# battleship.net
KiCad netlist of a schematic drawn in EAGLE
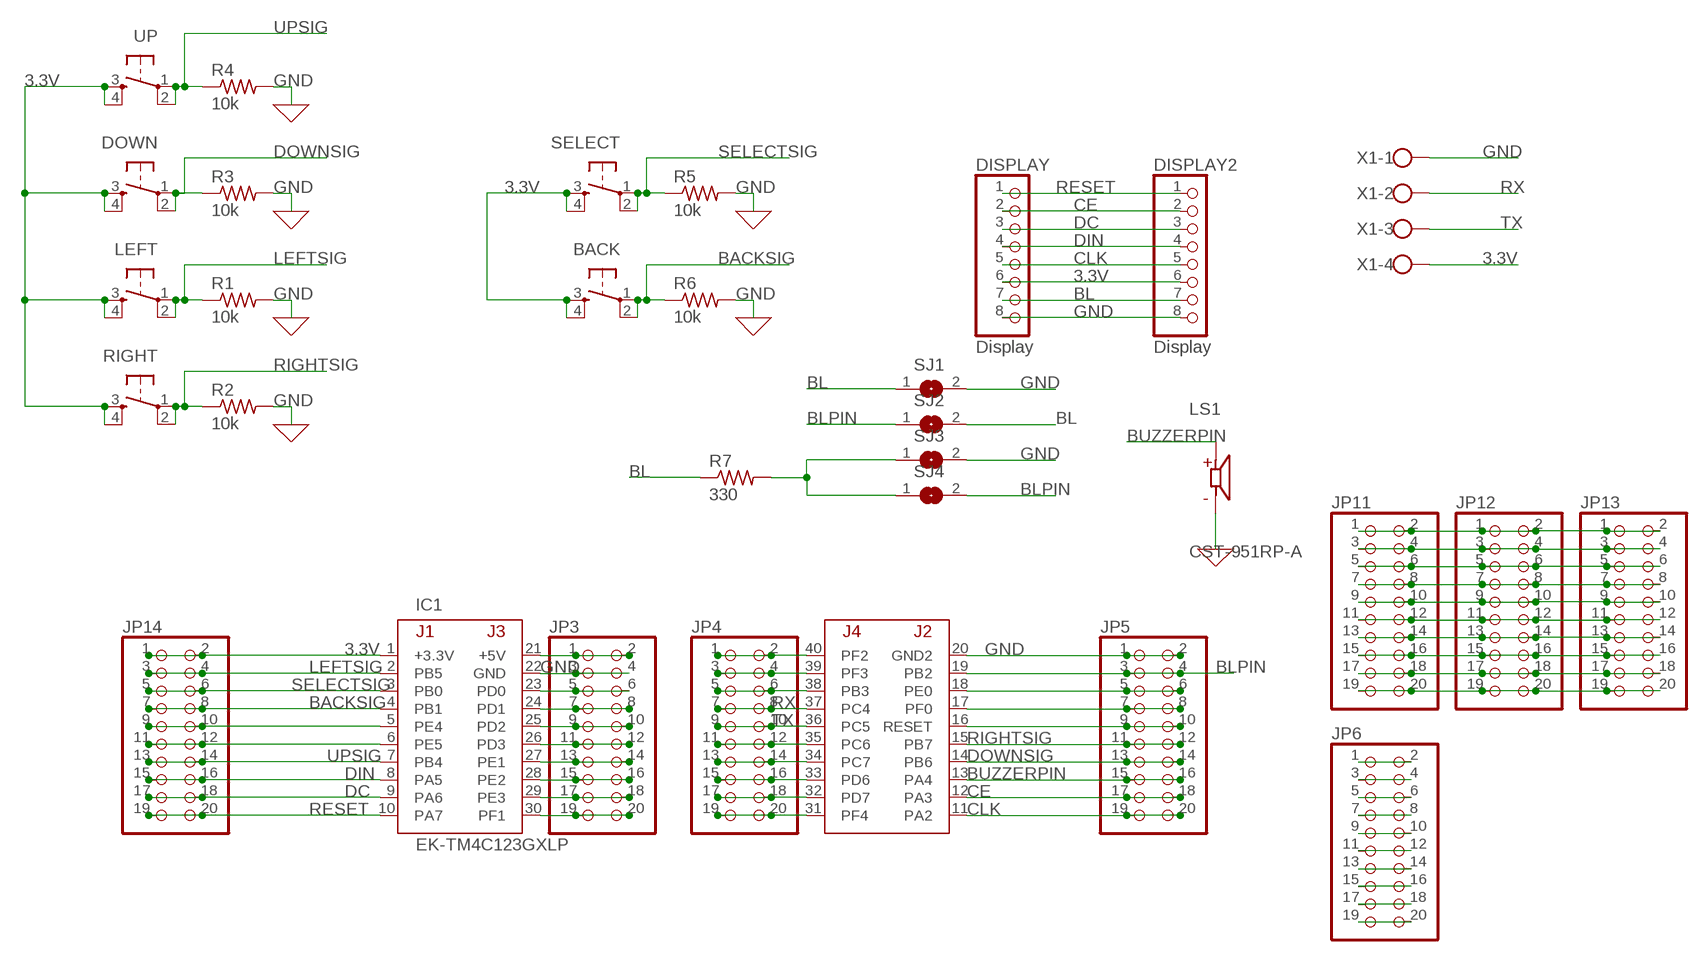
[diagram p0: schematic, sheet 1]

(export (version "E")
  (design (tool "Eeschema 10.0.6"))
  (components
    (comp (ref "BACK")
      (value "TAC_SWITCHPTH")
      (footprint "eagle-import:TACTILE-PTH")
      (libsource (lib "eagle-import") (part "TAC_SWITCHPTH"))
    )
    (comp (ref "DISPLAY")
      (value "Display")
      (footprint "eagle-import:1X08")
      (libsource (lib "eagle-import") (part "PINHD-1X8"))
    )
    (comp (ref "DISPLAY2")
      (value "Display")
      (footprint "eagle-import:1X08")
      (libsource (lib "eagle-import") (part "PINHD-1X8"))
    )
    (comp (ref "DOWN")
      (value "TAC_SWITCHPTH")
      (footprint "eagle-import:TACTILE-PTH")
      (libsource (lib "eagle-import") (part "TAC_SWITCHPTH"))
    )
    (comp (ref "IC1")
      (value "EK-TM4C123GXLP")
      (footprint "eagle-import:TM4C123LAUNCHPAD")
      (libsource (lib "eagle-import") (part "EK-TM4C123GXLP"))
    )
    (comp (ref "JP3")
      (value "PINHD-2X10")
      (footprint "eagle-import:2X10")
      (libsource (lib "eagle-import") (part "PINHD-2X10"))
    )
    (comp (ref "JP4")
      (value "PINHD-2X10")
      (footprint "eagle-import:2X10")
      (libsource (lib "eagle-import") (part "PINHD-2X10"))
    )
    (comp (ref "JP5")
      (value "PINHD-2X10")
      (footprint "eagle-import:2X10")
      (libsource (lib "eagle-import") (part "PINHD-2X10"))
    )
    (comp (ref "JP6")
      (value "PINHD-2X10")
      (footprint "eagle-import:2X10")
      (libsource (lib "eagle-import") (part "PINHD-2X10"))
    )
    (comp (ref "JP11")
      (value "PINHD-2X10")
      (footprint "eagle-import:2X10")
      (libsource (lib "eagle-import") (part "PINHD-2X10"))
    )
    (comp (ref "JP12")
      (value "PINHD-2X10")
      (footprint "eagle-import:2X10")
      (libsource (lib "eagle-import") (part "PINHD-2X10"))
    )
    (comp (ref "JP13")
      (value "PINHD-2X10")
      (footprint "eagle-import:2X10")
      (libsource (lib "eagle-import") (part "PINHD-2X10"))
    )
    (comp (ref "JP14")
      (value "PINHD-2X10")
      (footprint "eagle-import:2X10")
      (libsource (lib "eagle-import") (part "PINHD-2X10"))
    )
    (comp (ref "LEFT")
      (value "TAC_SWITCHPTH")
      (footprint "eagle-import:TACTILE-PTH")
      (libsource (lib "eagle-import") (part "TAC_SWITCHPTH"))
    )
    (comp (ref "LS1")
      (value "CST-951RP-A")
      (footprint "eagle-import:CUI_CST-951RP-A")
      (fields (field (name "MF") "CUI Inc."))
      (libsource (lib "eagle-import") (part "CST-951RP-A"))
    )
    (comp (ref "R1")
      (value "10k")
      (footprint "eagle-import:0207_10")
      (libsource (lib "eagle-import") (part "R-US_0207/10"))
    )
    (comp (ref "R2")
      (value "10k")
      (footprint "eagle-import:0207_10")
      (libsource (lib "eagle-import") (part "R-US_0207/10"))
    )
    (comp (ref "R3")
      (value "10k")
      (footprint "eagle-import:0207_10")
      (libsource (lib "eagle-import") (part "R-US_0207/10"))
    )
    (comp (ref "R4")
      (value "10k")
      (footprint "eagle-import:0207_10")
      (libsource (lib "eagle-import") (part "R-US_0207/10"))
    )
    (comp (ref "R5")
      (value "10k")
      (footprint "eagle-import:0207_10")
      (libsource (lib "eagle-import") (part "R-US_0207/10"))
    )
    (comp (ref "R6")
      (value "10k")
      (footprint "eagle-import:0207_10")
      (libsource (lib "eagle-import") (part "R-US_0207/10"))
    )
    (comp (ref "R7")
      (value "330")
      (footprint "eagle-import:0207_10")
      (libsource (lib "eagle-import") (part "R-US_0207/10"))
    )
    (comp (ref "RIGHT")
      (value "TAC_SWITCHPTH")
      (footprint "eagle-import:TACTILE-PTH")
      (libsource (lib "eagle-import") (part "TAC_SWITCHPTH"))
    )
    (comp (ref "SELECT")
      (value "TAC_SWITCHPTH")
      (footprint "eagle-import:TACTILE-PTH")
      (libsource (lib "eagle-import") (part "TAC_SWITCHPTH"))
    )
    (comp (ref "SJ1") (value "SJ") (footprint "eagle-import:SJ") (libsource (lib "eagle-import") (part "SJ")))
    (comp (ref "SJ2") (value "SJ") (footprint "eagle-import:SJ") (libsource (lib "eagle-import") (part "SJ")))
    (comp (ref "SJ3") (value "SJ") (footprint "eagle-import:SJ") (libsource (lib "eagle-import") (part "SJ")))
    (comp (ref "SJ4") (value "SJ") (footprint "eagle-import:SJ") (libsource (lib "eagle-import") (part "SJ")))
    (comp (ref "UP")
      (value "TAC_SWITCHPTH")
      (footprint "eagle-import:TACTILE-PTH")
      (libsource (lib "eagle-import") (part "TAC_SWITCHPTH"))
    )
    (comp (ref "X1")
      (value "W237-4")
      (footprint "eagle-import:W237-4")
      (libsource (lib "eagle-import") (part "W237-4"))
    )
  )
  (nets
    (net (code "1") (name "/3.3V") (class "Default")
      (node (ref "BACK") (pin "3") (pinfunction "3_3") (pintype "passive"))
      (node (ref "BACK") (pin "4") (pinfunction "4_4") (pintype "passive"))
      (node (ref "DISPLAY") (pin "6") (pinfunction "6_6") (pintype "passive"))
      (node (ref "DISPLAY2") (pin "6") (pinfunction "6_6") (pintype "passive"))
      (node (ref "DOWN") (pin "3") (pinfunction "3_3") (pintype "passive"))
      (node (ref "DOWN") (pin "4") (pinfunction "4_4") (pintype "passive"))
      (node (ref "IC1") (pin "1") (pinfunction "+3.3V_1") (pintype "power_in"))
      (node (ref "JP14") (pin "1") (pinfunction "1_1") (pintype "passive"))
      (node (ref "JP14") (pin "2") (pinfunction "2_2") (pintype "passive"))
      (node (ref "LEFT") (pin "3") (pinfunction "3_3") (pintype "passive"))
      (node (ref "LEFT") (pin "4") (pinfunction "4_4") (pintype "passive"))
      (node (ref "RIGHT") (pin "3") (pinfunction "3_3") (pintype "passive"))
      (node (ref "RIGHT") (pin "4") (pinfunction "4_4") (pintype "passive"))
      (node (ref "SELECT") (pin "3") (pinfunction "3_3") (pintype "passive"))
      (node (ref "SELECT") (pin "4") (pinfunction "4_4") (pintype "passive"))
      (node (ref "UP") (pin "3") (pinfunction "3_3") (pintype "passive"))
      (node (ref "UP") (pin "4") (pinfunction "4_4") (pintype "passive"))
      (node (ref "X1") (pin "4") (pinfunction "KL_4") (pintype "passive"))
    )
    (net (code "2") (name "/BACKSIG") (class "Default")
      (node (ref "BACK") (pin "1") (pinfunction "1_1") (pintype "passive"))
      (node (ref "BACK") (pin "2") (pinfunction "2_2") (pintype "passive"))
      (node (ref "IC1") (pin "4") (pinfunction "PB1_4") (pintype "bidirectional"))
      (node (ref "JP14") (pin "7") (pinfunction "7_7") (pintype "passive"))
      (node (ref "JP14") (pin "8") (pinfunction "8_8") (pintype "passive"))
      (node (ref "R6") (pin "1") (pinfunction "1_1") (pintype "passive"))
    )
    (net (code "3") (name "/BL") (class "Default")
      (node (ref "DISPLAY") (pin "7") (pinfunction "7_7") (pintype "passive"))
      (node (ref "DISPLAY2") (pin "7") (pinfunction "7_7") (pintype "passive"))
      (node (ref "R7") (pin "1") (pinfunction "1_1") (pintype "passive"))
      (node (ref "SJ1") (pin "1") (pinfunction "1_1") (pintype "passive"))
      (node (ref "SJ2") (pin "2") (pinfunction "2_2") (pintype "passive"))
    )
    (net (code "4") (name "/BLPIN") (class "Default")
      (node (ref "IC1") (pin "19") (pinfunction "PB2_19") (pintype "bidirectional"))
      (node (ref "JP5") (pin "3") (pinfunction "3_3") (pintype "passive"))
      (node (ref "JP5") (pin "4") (pinfunction "4_4") (pintype "passive"))
      (node (ref "SJ2") (pin "1") (pinfunction "1_1") (pintype "passive"))
      (node (ref "SJ4") (pin "2") (pinfunction "2_2") (pintype "passive"))
    )
    (net (code "5") (name "/BUZZERPIN") (class "Default")
      (node (ref "IC1") (pin "13") (pinfunction "PA4_13") (pintype "bidirectional"))
      (node (ref "JP5") (pin "15") (pinfunction "15_15") (pintype "passive"))
      (node (ref "JP5") (pin "16") (pinfunction "16_16") (pintype "passive"))
      (node (ref "LS1") (pin "P") (pinfunction "P_P") (pintype "passive"))
    )
    (net (code "6") (name "/CE") (class "Default")
      (node (ref "DISPLAY") (pin "2") (pinfunction "2_2") (pintype "passive"))
      (node (ref "DISPLAY2") (pin "2") (pinfunction "2_2") (pintype "passive"))
      (node (ref "IC1") (pin "12") (pinfunction "PA3_12") (pintype "bidirectional"))
      (node (ref "JP5") (pin "17") (pinfunction "17_17") (pintype "passive"))
      (node (ref "JP5") (pin "18") (pinfunction "18_18") (pintype "passive"))
    )
    (net (code "7") (name "/CLK") (class "Default")
      (node (ref "DISPLAY") (pin "5") (pinfunction "5_5") (pintype "passive"))
      (node (ref "DISPLAY2") (pin "5") (pinfunction "5_5") (pintype "passive"))
      (node (ref "IC1") (pin "11") (pinfunction "PA2_11") (pintype "bidirectional"))
      (node (ref "JP5") (pin "19") (pinfunction "19_19") (pintype "passive"))
      (node (ref "JP5") (pin "20") (pinfunction "20_20") (pintype "passive"))
    )
    (net (code "8") (name "/DC") (class "Default")
      (node (ref "DISPLAY") (pin "3") (pinfunction "3_3") (pintype "passive"))
      (node (ref "DISPLAY2") (pin "3") (pinfunction "3_3") (pintype "passive"))
      (node (ref "IC1") (pin "9") (pinfunction "PA6_9") (pintype "bidirectional"))
      (node (ref "JP14") (pin "17") (pinfunction "17_17") (pintype "passive"))
      (node (ref "JP14") (pin "18") (pinfunction "18_18") (pintype "passive"))
    )
    (net (code "9") (name "/DIN") (class "Default")
      (node (ref "DISPLAY") (pin "4") (pinfunction "4_4") (pintype "passive"))
      (node (ref "DISPLAY2") (pin "4") (pinfunction "4_4") (pintype "passive"))
      (node (ref "IC1") (pin "8") (pinfunction "PA5_8") (pintype "bidirectional"))
      (node (ref "JP14") (pin "15") (pinfunction "15_15") (pintype "passive"))
      (node (ref "JP14") (pin "16") (pinfunction "16_16") (pintype "passive"))
    )
    (net (code "10") (name "/DOWNSIG") (class "Default")
      (node (ref "DOWN") (pin "1") (pinfunction "1_1") (pintype "passive"))
      (node (ref "DOWN") (pin "2") (pinfunction "2_2") (pintype "passive"))
      (node (ref "IC1") (pin "14") (pinfunction "PB6_14") (pintype "bidirectional"))
      (node (ref "JP5") (pin "13") (pinfunction "13_13") (pintype "passive"))
      (node (ref "JP5") (pin "14") (pinfunction "14_14") (pintype "passive"))
      (node (ref "R3") (pin "1") (pinfunction "1_1") (pintype "passive"))
    )
    (net (code "11") (name "/LEFTSIG") (class "Default")
      (node (ref "IC1") (pin "2") (pinfunction "PB5_2") (pintype "bidirectional"))
      (node (ref "JP14") (pin "3") (pinfunction "3_3") (pintype "passive"))
      (node (ref "JP14") (pin "4") (pinfunction "4_4") (pintype "passive"))
      (node (ref "LEFT") (pin "1") (pinfunction "1_1") (pintype "passive"))
      (node (ref "LEFT") (pin "2") (pinfunction "2_2") (pintype "passive"))
      (node (ref "R1") (pin "1") (pinfunction "1_1") (pintype "passive"))
    )
    (net (code "12") (name "/RESET") (class "Default")
      (node (ref "DISPLAY") (pin "1") (pinfunction "1_1") (pintype "passive"))
      (node (ref "DISPLAY2") (pin "1") (pinfunction "1_1") (pintype "passive"))
      (node (ref "IC1") (pin "10") (pinfunction "PA7_10") (pintype "bidirectional"))
      (node (ref "JP14") (pin "19") (pinfunction "19_19") (pintype "passive"))
      (node (ref "JP14") (pin "20") (pinfunction "20_20") (pintype "passive"))
    )
    (net (code "13") (name "/RIGHTSIG") (class "Default")
      (node (ref "IC1") (pin "15") (pinfunction "PB7_15") (pintype "bidirectional"))
      (node (ref "JP5") (pin "11") (pinfunction "11_11") (pintype "passive"))
      (node (ref "JP5") (pin "12") (pinfunction "12_12") (pintype "passive"))
      (node (ref "R2") (pin "1") (pinfunction "1_1") (pintype "passive"))
      (node (ref "RIGHT") (pin "1") (pinfunction "1_1") (pintype "passive"))
      (node (ref "RIGHT") (pin "2") (pinfunction "2_2") (pintype "passive"))
    )
    (net (code "14") (name "/RX") (class "Default")
      (node (ref "IC1") (pin "37") (pinfunction "PC4_37") (pintype "bidirectional"))
      (node (ref "JP4") (pin "7") (pinfunction "7_7") (pintype "passive"))
      (node (ref "JP4") (pin "8") (pinfunction "8_8") (pintype "passive"))
      (node (ref "X1") (pin "2") (pinfunction "KL_2") (pintype "passive"))
    )
    (net (code "15") (name "/SELECTSIG") (class "Default")
      (node (ref "IC1") (pin "3") (pinfunction "PB0_3") (pintype "bidirectional"))
      (node (ref "JP14") (pin "5") (pinfunction "5_5") (pintype "passive"))
      (node (ref "JP14") (pin "6") (pinfunction "6_6") (pintype "passive"))
      (node (ref "R5") (pin "1") (pinfunction "1_1") (pintype "passive"))
      (node (ref "SELECT") (pin "1") (pinfunction "1_1") (pintype "passive"))
      (node (ref "SELECT") (pin "2") (pinfunction "2_2") (pintype "passive"))
    )
    (net (code "16") (name "/TX") (class "Default")
      (node (ref "IC1") (pin "36") (pinfunction "PC5_36") (pintype "bidirectional"))
      (node (ref "JP4") (pin "10") (pinfunction "10_10") (pintype "passive"))
      (node (ref "JP4") (pin "9") (pinfunction "9_9") (pintype "passive"))
      (node (ref "X1") (pin "3") (pinfunction "KL_3") (pintype "passive"))
    )
    (net (code "17") (name "/UPSIG") (class "Default")
      (node (ref "IC1") (pin "7") (pinfunction "PB4_7") (pintype "bidirectional"))
      (node (ref "JP14") (pin "13") (pinfunction "13_13") (pintype "passive"))
      (node (ref "JP14") (pin "14") (pinfunction "14_14") (pintype "passive"))
      (node (ref "R4") (pin "1") (pinfunction "1_1") (pintype "passive"))
      (node (ref "UP") (pin "1") (pinfunction "1_1") (pintype "passive"))
      (node (ref "UP") (pin "2") (pinfunction "2_2") (pintype "passive"))
    )
    (net (code "18") (name "GND") (class "Default")
      (node (ref "DISPLAY") (pin "8") (pinfunction "8_8") (pintype "passive"))
      (node (ref "DISPLAY2") (pin "8") (pinfunction "8_8") (pintype "passive"))
      (node (ref "IC1") (pin "20") (pinfunction "GND2_20") (pintype "power_in"))
      (node (ref "IC1") (pin "22") (pinfunction "GND_22") (pintype "power_in"))
      (node (ref "JP3") (pin "3") (pinfunction "3_3") (pintype "passive"))
      (node (ref "JP3") (pin "4") (pinfunction "4_4") (pintype "passive"))
      (node (ref "JP5") (pin "1") (pinfunction "1_1") (pintype "passive"))
      (node (ref "JP5") (pin "2") (pinfunction "2_2") (pintype "passive"))
      (node (ref "LS1") (pin "M") (pinfunction "M_M") (pintype "passive"))
      (node (ref "R1") (pin "2") (pinfunction "2_2") (pintype "passive"))
      (node (ref "R2") (pin "2") (pinfunction "2_2") (pintype "passive"))
      (node (ref "R3") (pin "2") (pinfunction "2_2") (pintype "passive"))
      (node (ref "R4") (pin "2") (pinfunction "2_2") (pintype "passive"))
      (node (ref "R5") (pin "2") (pinfunction "2_2") (pintype "passive"))
      (node (ref "R6") (pin "2") (pinfunction "2_2") (pintype "passive"))
      (node (ref "SJ1") (pin "2") (pinfunction "2_2") (pintype "passive"))
      (node (ref "SJ3") (pin "2") (pinfunction "2_2") (pintype "passive"))
      (node (ref "X1") (pin "1") (pinfunction "KL_1") (pintype "passive"))
    )
    (net (code "19") (name "Net-(IC1-+5V)") (class "Default")
      (node (ref "IC1") (pin "21") (pinfunction "+5V_21") (pintype "power_in"))
      (node (ref "JP3") (pin "1") (pinfunction "1_1") (pintype "passive"))
      (node (ref "JP3") (pin "2") (pinfunction "2_2") (pintype "passive"))
    )
    (net (code "20") (name "Net-(IC1-PB3)") (class "Default")
      (node (ref "IC1") (pin "38") (pinfunction "PB3_38") (pintype "bidirectional"))
      (node (ref "JP4") (pin "5") (pinfunction "5_5") (pintype "passive"))
      (node (ref "JP4") (pin "6") (pinfunction "6_6") (pintype "passive"))
    )
    (net (code "21") (name "Net-(IC1-PC6)") (class "Default")
      (node (ref "IC1") (pin "35") (pinfunction "PC6_35") (pintype "bidirectional"))
      (node (ref "JP4") (pin "11") (pinfunction "11_11") (pintype "passive"))
      (node (ref "JP4") (pin "12") (pinfunction "12_12") (pintype "passive"))
    )
    (net (code "22") (name "Net-(IC1-PC7)") (class "Default")
      (node (ref "IC1") (pin "34") (pinfunction "PC7_34") (pintype "bidirectional"))
      (node (ref "JP4") (pin "13") (pinfunction "13_13") (pintype "passive"))
      (node (ref "JP4") (pin "14") (pinfunction "14_14") (pintype "passive"))
    )
    (net (code "23") (name "Net-(IC1-PD0)") (class "Default")
      (node (ref "IC1") (pin "23") (pinfunction "PD0_23") (pintype "bidirectional"))
      (node (ref "JP3") (pin "5") (pinfunction "5_5") (pintype "passive"))
      (node (ref "JP3") (pin "6") (pinfunction "6_6") (pintype "passive"))
    )
    (net (code "24") (name "Net-(IC1-PD1)") (class "Default")
      (node (ref "IC1") (pin "24") (pinfunction "PD1_24") (pintype "bidirectional"))
      (node (ref "JP3") (pin "7") (pinfunction "7_7") (pintype "passive"))
      (node (ref "JP3") (pin "8") (pinfunction "8_8") (pintype "passive"))
    )
    (net (code "25") (name "Net-(IC1-PD2)") (class "Default")
      (node (ref "IC1") (pin "25") (pinfunction "PD2_25") (pintype "bidirectional"))
      (node (ref "JP3") (pin "10") (pinfunction "10_10") (pintype "passive"))
      (node (ref "JP3") (pin "9") (pinfunction "9_9") (pintype "passive"))
    )
    (net (code "26") (name "Net-(IC1-PD3)") (class "Default")
      (node (ref "IC1") (pin "26") (pinfunction "PD3_26") (pintype "bidirectional"))
      (node (ref "JP3") (pin "11") (pinfunction "11_11") (pintype "passive"))
      (node (ref "JP3") (pin "12") (pinfunction "12_12") (pintype "passive"))
    )
    (net (code "27") (name "Net-(IC1-PD6)") (class "Default")
      (node (ref "IC1") (pin "33") (pinfunction "PD6_33") (pintype "bidirectional"))
      (node (ref "JP4") (pin "15") (pinfunction "15_15") (pintype "passive"))
      (node (ref "JP4") (pin "16") (pinfunction "16_16") (pintype "passive"))
    )
    (net (code "28") (name "Net-(IC1-PD7)") (class "Default")
      (node (ref "IC1") (pin "32") (pinfunction "PD7_32") (pintype "bidirectional"))
      (node (ref "JP4") (pin "17") (pinfunction "17_17") (pintype "passive"))
      (node (ref "JP4") (pin "18") (pinfunction "18_18") (pintype "passive"))
    )
    (net (code "29") (name "Net-(IC1-PE0)") (class "Default")
      (node (ref "IC1") (pin "18") (pinfunction "PE0_18") (pintype "bidirectional"))
      (node (ref "JP5") (pin "5") (pinfunction "5_5") (pintype "passive"))
      (node (ref "JP5") (pin "6") (pinfunction "6_6") (pintype "passive"))
    )
    (net (code "30") (name "Net-(IC1-PE1)") (class "Default")
      (node (ref "IC1") (pin "27") (pinfunction "PE1_27") (pintype "bidirectional"))
      (node (ref "JP3") (pin "13") (pinfunction "13_13") (pintype "passive"))
      (node (ref "JP3") (pin "14") (pinfunction "14_14") (pintype "passive"))
    )
    (net (code "31") (name "Net-(IC1-PE2)") (class "Default")
      (node (ref "IC1") (pin "28") (pinfunction "PE2_28") (pintype "bidirectional"))
      (node (ref "JP3") (pin "15") (pinfunction "15_15") (pintype "passive"))
      (node (ref "JP3") (pin "16") (pinfunction "16_16") (pintype "passive"))
    )
    (net (code "32") (name "Net-(IC1-PE3)") (class "Default")
      (node (ref "IC1") (pin "29") (pinfunction "PE3_29") (pintype "bidirectional"))
      (node (ref "JP3") (pin "17") (pinfunction "17_17") (pintype "passive"))
      (node (ref "JP3") (pin "18") (pinfunction "18_18") (pintype "passive"))
    )
    (net (code "33") (name "Net-(IC1-PE4)") (class "Default")
      (node (ref "IC1") (pin "5") (pinfunction "PE4_5") (pintype "bidirectional"))
      (node (ref "JP14") (pin "10") (pinfunction "10_10") (pintype "passive"))
      (node (ref "JP14") (pin "9") (pinfunction "9_9") (pintype "passive"))
    )
    (net (code "34") (name "Net-(IC1-PE5)") (class "Default")
      (node (ref "IC1") (pin "6") (pinfunction "PE5_6") (pintype "bidirectional"))
      (node (ref "JP14") (pin "11") (pinfunction "11_11") (pintype "passive"))
      (node (ref "JP14") (pin "12") (pinfunction "12_12") (pintype "passive"))
    )
    (net (code "35") (name "Net-(IC1-PF0)") (class "Default")
      (node (ref "IC1") (pin "17") (pinfunction "PF0_17") (pintype "bidirectional"))
      (node (ref "JP5") (pin "7") (pinfunction "7_7") (pintype "passive"))
      (node (ref "JP5") (pin "8") (pinfunction "8_8") (pintype "passive"))
    )
    (net (code "36") (name "Net-(IC1-PF1)") (class "Default")
      (node (ref "IC1") (pin "30") (pinfunction "PF1_30") (pintype "bidirectional"))
      (node (ref "JP3") (pin "19") (pinfunction "19_19") (pintype "passive"))
      (node (ref "JP3") (pin "20") (pinfunction "20_20") (pintype "passive"))
    )
    (net (code "37") (name "Net-(IC1-PF2)") (class "Default")
      (node (ref "IC1") (pin "40") (pinfunction "PF2_40") (pintype "bidirectional"))
      (node (ref "JP4") (pin "1") (pinfunction "1_1") (pintype "passive"))
      (node (ref "JP4") (pin "2") (pinfunction "2_2") (pintype "passive"))
    )
    (net (code "38") (name "Net-(IC1-PF3)") (class "Default")
      (node (ref "IC1") (pin "39") (pinfunction "PF3_39") (pintype "bidirectional"))
      (node (ref "JP4") (pin "3") (pinfunction "3_3") (pintype "passive"))
      (node (ref "JP4") (pin "4") (pinfunction "4_4") (pintype "passive"))
    )
    (net (code "39") (name "Net-(IC1-PF4)") (class "Default")
      (node (ref "IC1") (pin "31") (pinfunction "PF4_31") (pintype "bidirectional"))
      (node (ref "JP4") (pin "19") (pinfunction "19_19") (pintype "passive"))
      (node (ref "JP4") (pin "20") (pinfunction "20_20") (pintype "passive"))
    )
    (net (code "40") (name "Net-(IC1-RESET)") (class "Default")
      (node (ref "IC1") (pin "16") (pinfunction "RESET_16") (pintype "input"))
      (node (ref "JP5") (pin "10") (pinfunction "10_10") (pintype "passive"))
      (node (ref "JP5") (pin "9") (pinfunction "9_9") (pintype "passive"))
    )
    (net (code "41") (name "Net-(JP6-Pad1)") (class "Default")
      (node (ref "JP6") (pin "1") (pinfunction "1_1") (pintype "passive"))
      (node (ref "JP6") (pin "2") (pinfunction "2_2") (pintype "passive"))
    )
    (net (code "42") (name "Net-(JP6-Pad3)") (class "Default")
      (node (ref "JP6") (pin "3") (pinfunction "3_3") (pintype "passive"))
      (node (ref "JP6") (pin "4") (pinfunction "4_4") (pintype "passive"))
    )
    (net (code "43") (name "Net-(JP6-Pad5)") (class "Default")
      (node (ref "JP6") (pin "5") (pinfunction "5_5") (pintype "passive"))
      (node (ref "JP6") (pin "6") (pinfunction "6_6") (pintype "passive"))
    )
    (net (code "44") (name "Net-(JP6-Pad7)") (class "Default")
      (node (ref "JP6") (pin "7") (pinfunction "7_7") (pintype "passive"))
      (node (ref "JP6") (pin "8") (pinfunction "8_8") (pintype "passive"))
    )
    (net (code "45") (name "Net-(JP6-Pad10)") (class "Default")
      (node (ref "JP6") (pin "10") (pinfunction "10_10") (pintype "passive"))
      (node (ref "JP6") (pin "9") (pinfunction "9_9") (pintype "passive"))
    )
    (net (code "46") (name "Net-(JP6-Pad11)") (class "Default")
      (node (ref "JP6") (pin "11") (pinfunction "11_11") (pintype "passive"))
      (node (ref "JP6") (pin "12") (pinfunction "12_12") (pintype "passive"))
    )
    (net (code "47") (name "Net-(JP6-Pad13)") (class "Default")
      (node (ref "JP6") (pin "13") (pinfunction "13_13") (pintype "passive"))
      (node (ref "JP6") (pin "14") (pinfunction "14_14") (pintype "passive"))
    )
    (net (code "48") (name "Net-(JP6-Pad15)") (class "Default")
      (node (ref "JP6") (pin "15") (pinfunction "15_15") (pintype "passive"))
      (node (ref "JP6") (pin "16") (pinfunction "16_16") (pintype "passive"))
    )
    (net (code "49") (name "Net-(JP6-Pad17)") (class "Default")
      (node (ref "JP6") (pin "17") (pinfunction "17_17") (pintype "passive"))
      (node (ref "JP6") (pin "18") (pinfunction "18_18") (pintype "passive"))
    )
    (net (code "50") (name "Net-(JP6-Pad19)") (class "Default")
      (node (ref "JP6") (pin "19") (pinfunction "19_19") (pintype "passive"))
      (node (ref "JP6") (pin "20") (pinfunction "20_20") (pintype "passive"))
    )
    (net (code "51") (name "Net-(JP11-Pad1)") (class "Default")
      (node (ref "JP11") (pin "1") (pinfunction "1_1") (pintype "passive"))
      (node (ref "JP11") (pin "2") (pinfunction "2_2") (pintype "passive"))
      (node (ref "JP12") (pin "1") (pinfunction "1_1") (pintype "passive"))
      (node (ref "JP12") (pin "2") (pinfunction "2_2") (pintype "passive"))
      (node (ref "JP13") (pin "1") (pinfunction "1_1") (pintype "passive"))
      (node (ref "JP13") (pin "2") (pinfunction "2_2") (pintype "passive"))
    )
    (net (code "52") (name "Net-(JP11-Pad3)") (class "Default")
      (node (ref "JP11") (pin "3") (pinfunction "3_3") (pintype "passive"))
      (node (ref "JP11") (pin "4") (pinfunction "4_4") (pintype "passive"))
      (node (ref "JP12") (pin "3") (pinfunction "3_3") (pintype "passive"))
      (node (ref "JP12") (pin "4") (pinfunction "4_4") (pintype "passive"))
      (node (ref "JP13") (pin "3") (pinfunction "3_3") (pintype "passive"))
      (node (ref "JP13") (pin "4") (pinfunction "4_4") (pintype "passive"))
    )
    (net (code "53") (name "Net-(JP11-Pad5)") (class "Default")
      (node (ref "JP11") (pin "5") (pinfunction "5_5") (pintype "passive"))
      (node (ref "JP11") (pin "6") (pinfunction "6_6") (pintype "passive"))
      (node (ref "JP12") (pin "5") (pinfunction "5_5") (pintype "passive"))
      (node (ref "JP12") (pin "6") (pinfunction "6_6") (pintype "passive"))
      (node (ref "JP13") (pin "5") (pinfunction "5_5") (pintype "passive"))
      (node (ref "JP13") (pin "6") (pinfunction "6_6") (pintype "passive"))
    )
    (net (code "54") (name "Net-(JP11-Pad7)") (class "Default")
      (node (ref "JP11") (pin "7") (pinfunction "7_7") (pintype "passive"))
      (node (ref "JP11") (pin "8") (pinfunction "8_8") (pintype "passive"))
      (node (ref "JP12") (pin "7") (pinfunction "7_7") (pintype "passive"))
      (node (ref "JP12") (pin "8") (pinfunction "8_8") (pintype "passive"))
      (node (ref "JP13") (pin "7") (pinfunction "7_7") (pintype "passive"))
      (node (ref "JP13") (pin "8") (pinfunction "8_8") (pintype "passive"))
    )
    (net (code "55") (name "Net-(JP11-Pad10)") (class "Default")
      (node (ref "JP11") (pin "10") (pinfunction "10_10") (pintype "passive"))
      (node (ref "JP11") (pin "9") (pinfunction "9_9") (pintype "passive"))
      (node (ref "JP12") (pin "10") (pinfunction "10_10") (pintype "passive"))
      (node (ref "JP12") (pin "9") (pinfunction "9_9") (pintype "passive"))
      (node (ref "JP13") (pin "10") (pinfunction "10_10") (pintype "passive"))
      (node (ref "JP13") (pin "9") (pinfunction "9_9") (pintype "passive"))
    )
    (net (code "56") (name "Net-(JP11-Pad11)") (class "Default")
      (node (ref "JP11") (pin "11") (pinfunction "11_11") (pintype "passive"))
      (node (ref "JP11") (pin "12") (pinfunction "12_12") (pintype "passive"))
      (node (ref "JP12") (pin "11") (pinfunction "11_11") (pintype "passive"))
      (node (ref "JP12") (pin "12") (pinfunction "12_12") (pintype "passive"))
      (node (ref "JP13") (pin "11") (pinfunction "11_11") (pintype "passive"))
      (node (ref "JP13") (pin "12") (pinfunction "12_12") (pintype "passive"))
    )
    (net (code "57") (name "Net-(JP11-Pad13)") (class "Default")
      (node (ref "JP11") (pin "13") (pinfunction "13_13") (pintype "passive"))
      (node (ref "JP11") (pin "14") (pinfunction "14_14") (pintype "passive"))
      (node (ref "JP12") (pin "13") (pinfunction "13_13") (pintype "passive"))
      (node (ref "JP12") (pin "14") (pinfunction "14_14") (pintype "passive"))
      (node (ref "JP13") (pin "13") (pinfunction "13_13") (pintype "passive"))
      (node (ref "JP13") (pin "14") (pinfunction "14_14") (pintype "passive"))
    )
    (net (code "58") (name "Net-(JP11-Pad15)") (class "Default")
      (node (ref "JP11") (pin "15") (pinfunction "15_15") (pintype "passive"))
      (node (ref "JP11") (pin "16") (pinfunction "16_16") (pintype "passive"))
      (node (ref "JP12") (pin "15") (pinfunction "15_15") (pintype "passive"))
      (node (ref "JP12") (pin "16") (pinfunction "16_16") (pintype "passive"))
      (node (ref "JP13") (pin "15") (pinfunction "15_15") (pintype "passive"))
      (node (ref "JP13") (pin "16") (pinfunction "16_16") (pintype "passive"))
    )
    (net (code "59") (name "Net-(JP11-Pad17)") (class "Default")
      (node (ref "JP11") (pin "17") (pinfunction "17_17") (pintype "passive"))
      (node (ref "JP11") (pin "18") (pinfunction "18_18") (pintype "passive"))
      (node (ref "JP12") (pin "17") (pinfunction "17_17") (pintype "passive"))
      (node (ref "JP12") (pin "18") (pinfunction "18_18") (pintype "passive"))
      (node (ref "JP13") (pin "17") (pinfunction "17_17") (pintype "passive"))
      (node (ref "JP13") (pin "18") (pinfunction "18_18") (pintype "passive"))
    )
    (net (code "60") (name "Net-(JP11-Pad19)") (class "Default")
      (node (ref "JP11") (pin "19") (pinfunction "19_19") (pintype "passive"))
      (node (ref "JP11") (pin "20") (pinfunction "20_20") (pintype "passive"))
      (node (ref "JP12") (pin "19") (pinfunction "19_19") (pintype "passive"))
      (node (ref "JP12") (pin "20") (pinfunction "20_20") (pintype "passive"))
      (node (ref "JP13") (pin "19") (pinfunction "19_19") (pintype "passive"))
      (node (ref "JP13") (pin "20") (pinfunction "20_20") (pintype "passive"))
    )
    (net (code "61") (name "Net-(R7-Pad2)") (class "Default")
      (node (ref "R7") (pin "2") (pinfunction "2_2") (pintype "passive"))
      (node (ref "SJ3") (pin "1") (pinfunction "1_1") (pintype "passive"))
      (node (ref "SJ4") (pin "1") (pinfunction "1_1") (pintype "passive"))
    )
  )
)
